# B130X.net
KiCad netlist of a schematic drawn in EAGLE
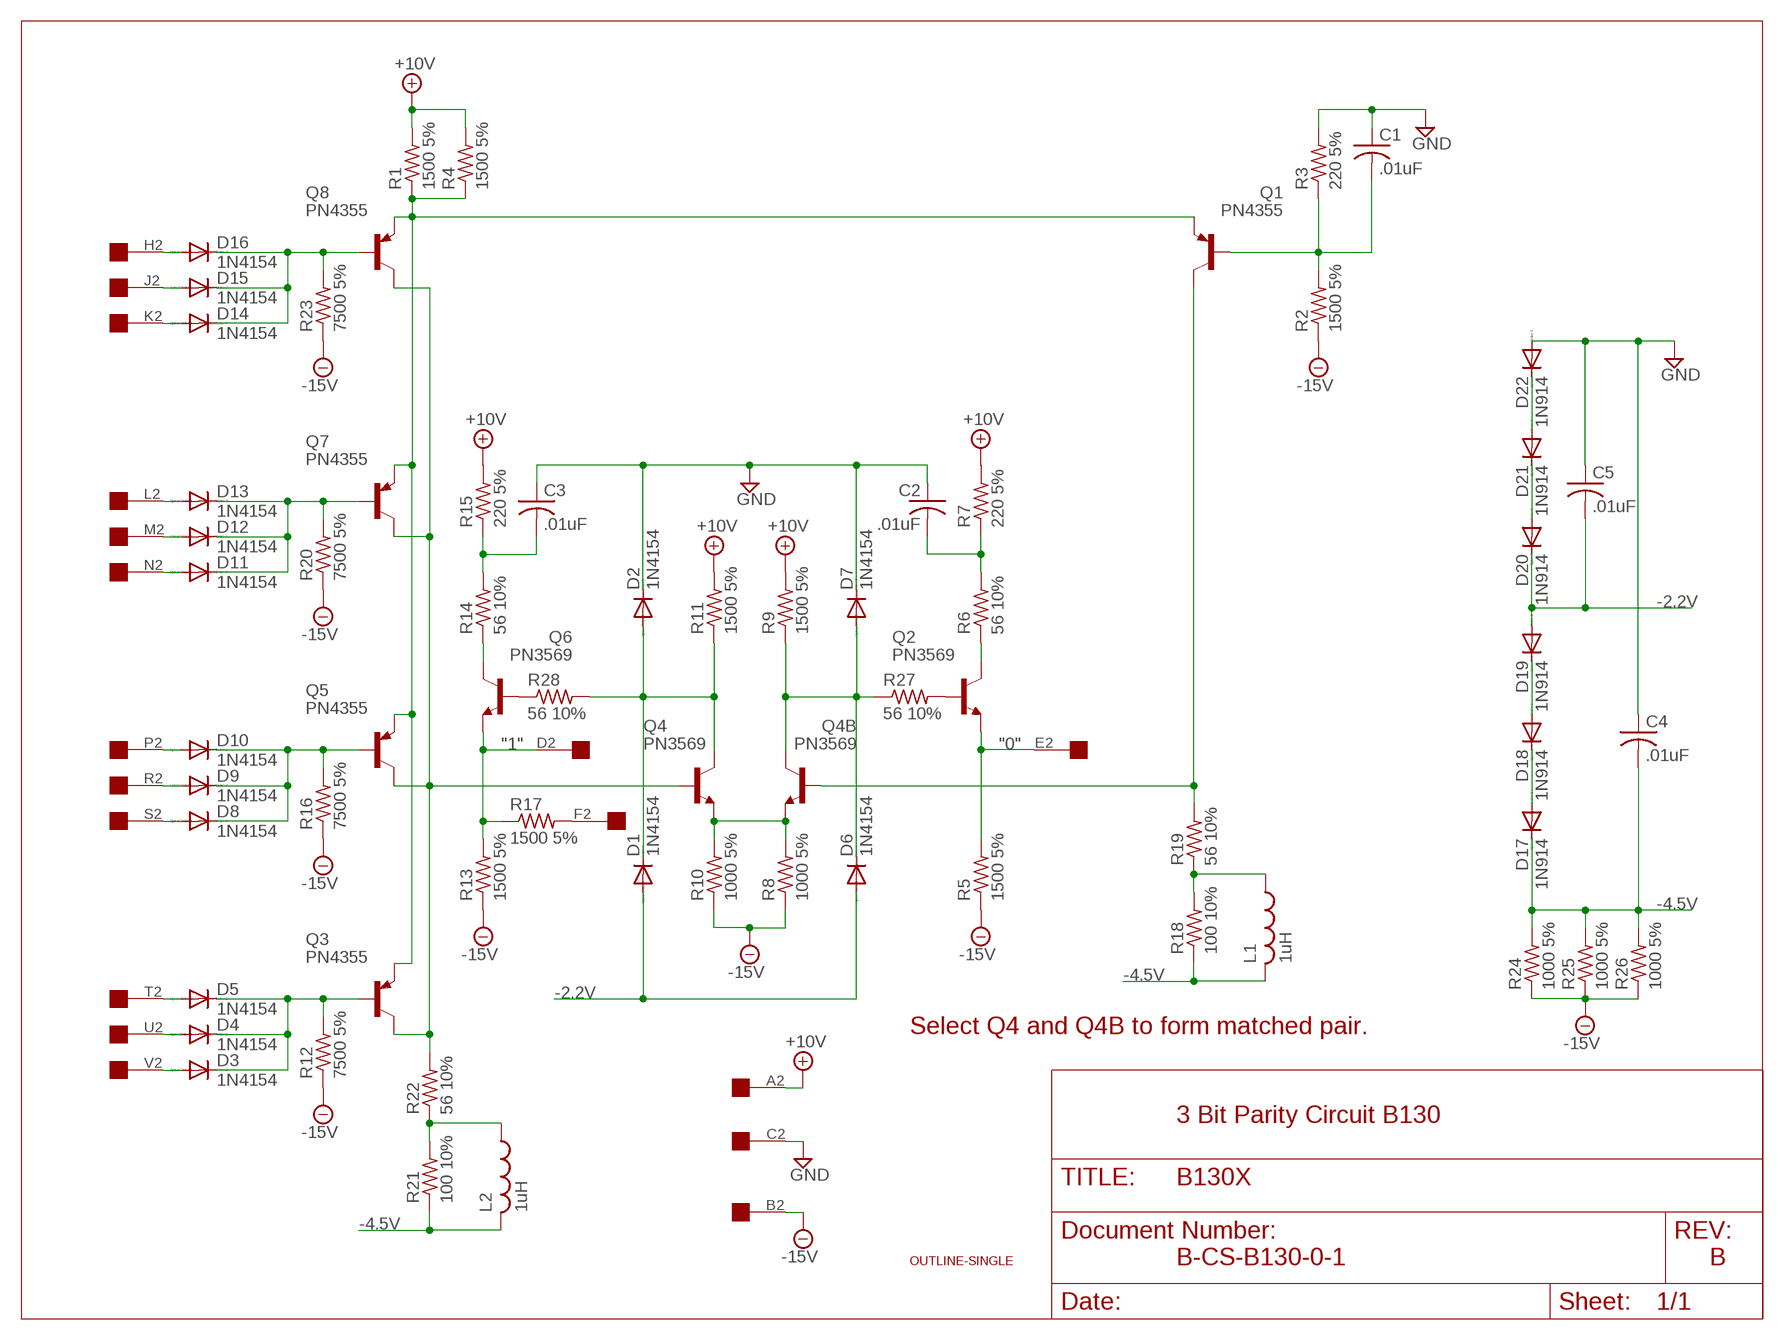
[diagram p0: schematic, sheet 1]

(export (version "E")
  (design (tool "Eeschema 10.0.6"))
  (components
    (comp (ref "C1")
      (value ".01uF")
      (footprint "eagle-import:C050-025X075")
      (libsource (lib "eagle-import") (part "C-US050-025X075"))
    )
    (comp (ref "C2")
      (value ".01uF")
      (footprint "eagle-import:C050-025X075")
      (libsource (lib "eagle-import") (part "C-US050-025X075"))
    )
    (comp (ref "C3")
      (value ".01uF")
      (footprint "eagle-import:C050-025X075")
      (libsource (lib "eagle-import") (part "C-US050-025X075"))
    )
    (comp (ref "C4")
      (value ".01uF")
      (footprint "eagle-import:C050-025X075")
      (libsource (lib "eagle-import") (part "C-US050-025X075"))
    )
    (comp (ref "C5")
      (value ".01uF")
      (footprint "eagle-import:C050-025X075")
      (libsource (lib "eagle-import") (part "C-US050-025X075"))
    )
    (comp (ref "D1")
      (value "1N4154")
      (footprint "eagle-import:DO35-10")
      (libsource (lib "eagle-import") (part "1N4148DO35-10"))
    )
    (comp (ref "D2")
      (value "1N4154")
      (footprint "eagle-import:DO35-10")
      (libsource (lib "eagle-import") (part "1N4148DO35-10"))
    )
    (comp (ref "D3")
      (value "1N4154")
      (footprint "eagle-import:DO35-10")
      (libsource (lib "eagle-import") (part "1N4148DO35-10"))
    )
    (comp (ref "D4")
      (value "1N4154")
      (footprint "eagle-import:DO35-10")
      (libsource (lib "eagle-import") (part "1N4148DO35-10"))
    )
    (comp (ref "D5")
      (value "1N4154")
      (footprint "eagle-import:DO35-10")
      (libsource (lib "eagle-import") (part "1N4148DO35-10"))
    )
    (comp (ref "D6")
      (value "1N4154")
      (footprint "eagle-import:DO35-10")
      (libsource (lib "eagle-import") (part "1N4148DO35-10"))
    )
    (comp (ref "D7")
      (value "1N4154")
      (footprint "eagle-import:DO35-10")
      (libsource (lib "eagle-import") (part "1N4148DO35-10"))
    )
    (comp (ref "D8")
      (value "1N4154")
      (footprint "eagle-import:DO35-10")
      (libsource (lib "eagle-import") (part "1N4148DO35-10"))
    )
    (comp (ref "D9")
      (value "1N4154")
      (footprint "eagle-import:DO35-10")
      (libsource (lib "eagle-import") (part "1N4148DO35-10"))
    )
    (comp (ref "D10")
      (value "1N4154")
      (footprint "eagle-import:DO35-10")
      (libsource (lib "eagle-import") (part "1N4148DO35-10"))
    )
    (comp (ref "D11")
      (value "1N4154")
      (footprint "eagle-import:DO35-10")
      (libsource (lib "eagle-import") (part "1N4148DO35-10"))
    )
    (comp (ref "D12")
      (value "1N4154")
      (footprint "eagle-import:DO35-10")
      (libsource (lib "eagle-import") (part "1N4148DO35-10"))
    )
    (comp (ref "D13")
      (value "1N4154")
      (footprint "eagle-import:DO35-10")
      (libsource (lib "eagle-import") (part "1N4148DO35-10"))
    )
    (comp (ref "D14")
      (value "1N4154")
      (footprint "eagle-import:DO35-10")
      (libsource (lib "eagle-import") (part "1N4148DO35-10"))
    )
    (comp (ref "D15")
      (value "1N4154")
      (footprint "eagle-import:DO35-10")
      (libsource (lib "eagle-import") (part "1N4148DO35-10"))
    )
    (comp (ref "D16")
      (value "1N4154")
      (footprint "eagle-import:DO35-10")
      (libsource (lib "eagle-import") (part "1N4148DO35-10"))
    )
    (comp (ref "D17")
      (value "1N914")
      (footprint "eagle-import:DO35-10")
      (libsource (lib "eagle-import") (part "1N4148DO35-10"))
    )
    (comp (ref "D18")
      (value "1N914")
      (footprint "eagle-import:DO35-10")
      (libsource (lib "eagle-import") (part "1N4148DO35-10"))
    )
    (comp (ref "D19")
      (value "1N914")
      (footprint "eagle-import:DO35-10")
      (libsource (lib "eagle-import") (part "1N4148DO35-10"))
    )
    (comp (ref "D20")
      (value "1N914")
      (footprint "eagle-import:DO35-10")
      (libsource (lib "eagle-import") (part "1N4148DO35-10"))
    )
    (comp (ref "D21")
      (value "1N914")
      (footprint "eagle-import:DO35-10")
      (libsource (lib "eagle-import") (part "1N4148DO35-10"))
    )
    (comp (ref "D22")
      (value "1N914")
      (footprint "eagle-import:DO35-10")
      (libsource (lib "eagle-import") (part "1N4148DO35-10"))
    )
    (comp (ref "L1")
      (value "1uH")
      (footprint "eagle-import:0207_10")
      (libsource (lib "eagle-import") (part "L-US0207/10"))
    )
    (comp (ref "L2")
      (value "1uH")
      (footprint "eagle-import:0207_10")
      (libsource (lib "eagle-import") (part "L-US0207/10"))
    )
    (comp (ref "Q1")
      (value "PN4355")
      (footprint "eagle-import:TO39")
      (libsource (lib "eagle-import") (part "2N2904"))
    )
    (comp (ref "Q2")
      (value "PN3569")
      (footprint "eagle-import:TO5")
      (libsource (lib "eagle-import") (part "2N2102"))
    )
    (comp (ref "Q3")
      (value "PN4355")
      (footprint "eagle-import:TO39")
      (libsource (lib "eagle-import") (part "2N2904"))
    )
    (comp (ref "Q4")
      (value "PN3569")
      (footprint "eagle-import:TO5")
      (libsource (lib "eagle-import") (part "2N2102"))
    )
    (comp (ref "Q4B")
      (value "PN3569")
      (footprint "eagle-import:TO5")
      (libsource (lib "eagle-import") (part "2N2102"))
    )
    (comp (ref "Q5")
      (value "PN4355")
      (footprint "eagle-import:TO39")
      (libsource (lib "eagle-import") (part "2N2904"))
    )
    (comp (ref "Q6")
      (value "PN3569")
      (footprint "eagle-import:TO5")
      (libsource (lib "eagle-import") (part "2N2102"))
    )
    (comp (ref "Q7")
      (value "PN4355")
      (footprint "eagle-import:TO39")
      (libsource (lib "eagle-import") (part "2N2904"))
    )
    (comp (ref "Q8")
      (value "PN4355")
      (footprint "eagle-import:TO39")
      (libsource (lib "eagle-import") (part "2N2904"))
    )
    (comp (ref "R1")
      (value "1500 5%")
      (footprint "eagle-import:0207_10")
      (libsource (lib "eagle-import") (part "R-US_0207/10"))
    )
    (comp (ref "R2")
      (value "1500 5%")
      (footprint "eagle-import:0207_10")
      (libsource (lib "eagle-import") (part "R-US_0207/10"))
    )
    (comp (ref "R3")
      (value "220 5%")
      (footprint "eagle-import:0207_10")
      (libsource (lib "eagle-import") (part "R-US_0207/10"))
    )
    (comp (ref "R4")
      (value "1500 5%")
      (footprint "eagle-import:0207_10")
      (libsource (lib "eagle-import") (part "R-US_0207/10"))
    )
    (comp (ref "R5")
      (value "1500 5%")
      (footprint "eagle-import:0207_10")
      (libsource (lib "eagle-import") (part "R-US_0207/10"))
    )
    (comp (ref "R6")
      (value "56 10%")
      (footprint "eagle-import:0207_10")
      (libsource (lib "eagle-import") (part "R-US_0207/10"))
    )
    (comp (ref "R7")
      (value "220 5%")
      (footprint "eagle-import:0207_10")
      (libsource (lib "eagle-import") (part "R-US_0207/10"))
    )
    (comp (ref "R8")
      (value "1000 5%")
      (footprint "eagle-import:0207_10")
      (libsource (lib "eagle-import") (part "R-US_0207/10"))
    )
    (comp (ref "R9")
      (value "1500 5%")
      (footprint "eagle-import:0207_10")
      (libsource (lib "eagle-import") (part "R-US_0207/10"))
    )
    (comp (ref "R10")
      (value "1000 5%")
      (footprint "eagle-import:0207_10")
      (libsource (lib "eagle-import") (part "R-US_0207/10"))
    )
    (comp (ref "R11")
      (value "1500 5%")
      (footprint "eagle-import:0207_10")
      (libsource (lib "eagle-import") (part "R-US_0207/10"))
    )
    (comp (ref "R12")
      (value "7500 5%")
      (footprint "eagle-import:0207_10")
      (libsource (lib "eagle-import") (part "R-US_0207/10"))
    )
    (comp (ref "R13")
      (value "1500 5%")
      (footprint "eagle-import:0207_10")
      (libsource (lib "eagle-import") (part "R-US_0207/10"))
    )
    (comp (ref "R14")
      (value "56 10%")
      (footprint "eagle-import:0207_10")
      (libsource (lib "eagle-import") (part "R-US_0207/10"))
    )
    (comp (ref "R15")
      (value "220 5%")
      (footprint "eagle-import:0207_10")
      (libsource (lib "eagle-import") (part "R-US_0207/10"))
    )
    (comp (ref "R16")
      (value "7500 5%")
      (footprint "eagle-import:0207_10")
      (libsource (lib "eagle-import") (part "R-US_0207/10"))
    )
    (comp (ref "R17")
      (value "1500 5%")
      (footprint "eagle-import:0207_10")
      (libsource (lib "eagle-import") (part "R-US_0207/10"))
    )
    (comp (ref "R18")
      (value "100 10%")
      (footprint "eagle-import:0207_10")
      (libsource (lib "eagle-import") (part "R-US_0207/10"))
    )
    (comp (ref "R19")
      (value "56 10%")
      (footprint "eagle-import:0207_10")
      (libsource (lib "eagle-import") (part "R-US_0207/10"))
    )
    (comp (ref "R20")
      (value "7500 5%")
      (footprint "eagle-import:0207_10")
      (libsource (lib "eagle-import") (part "R-US_0207/10"))
    )
    (comp (ref "R21")
      (value "100 10%")
      (footprint "eagle-import:0207_10")
      (libsource (lib "eagle-import") (part "R-US_0207/10"))
    )
    (comp (ref "R22")
      (value "56 10%")
      (footprint "eagle-import:0207_10")
      (libsource (lib "eagle-import") (part "R-US_0207/10"))
    )
    (comp (ref "R23")
      (value "7500 5%")
      (footprint "eagle-import:0207_10")
      (libsource (lib "eagle-import") (part "R-US_0207/10"))
    )
    (comp (ref "R24")
      (value "1000 5%")
      (footprint "eagle-import:0207_10")
      (libsource (lib "eagle-import") (part "R-US_0207/10"))
    )
    (comp (ref "R25")
      (value "1000 5%")
      (footprint "eagle-import:0207_10")
      (libsource (lib "eagle-import") (part "R-US_0207/10"))
    )
    (comp (ref "R26")
      (value "1000 5%")
      (footprint "eagle-import:0207_10")
      (libsource (lib "eagle-import") (part "R-US_0207/10"))
    )
    (comp (ref "R27")
      (value "56 10%")
      (footprint "eagle-import:0207_10")
      (libsource (lib "eagle-import") (part "R-US_0207/10"))
    )
    (comp (ref "R28")
      (value "56 10%")
      (footprint "eagle-import:0207_10")
      (libsource (lib "eagle-import") (part "R-US_0207/10"))
    )
    (comp (ref "U$1")
      (value "OUTLINE-SINGLE")
      (footprint "eagle-import:SINGLE")
      (libsource (lib "eagle-import") (part "OUTLINE-SINGLE"))
    )
    (comp (ref "U$2")
      (value "EDGE-1")
      (footprint "eagle-import:EDGE-CON1")
      (libsource (lib "eagle-import") (part "EDGE-1"))
    )
  )
  (nets
    (net (code "1") (name "+10V") (class "Default")
      (node (ref "R1") (pin "2") (pinfunction "2_2") (pintype "passive"))
      (node (ref "R11") (pin "2") (pinfunction "2_2") (pintype "passive"))
      (node (ref "R15") (pin "2") (pinfunction "2_2") (pintype "passive"))
      (node (ref "R4") (pin "2") (pinfunction "2_2") (pintype "passive"))
      (node (ref "R7") (pin "2") (pinfunction "2_2") (pintype "passive"))
      (node (ref "R9") (pin "2") (pinfunction "2_2") (pintype "passive"))
      (node (ref "U$2") (pin "A2") (pinfunction "1_A2") (pintype "bidirectional"))
    )
    (net (code "2") (name "-15V") (class "Default")
      (node (ref "R10") (pin "1") (pinfunction "1_1") (pintype "passive"))
      (node (ref "R12") (pin "1") (pinfunction "1_1") (pintype "passive"))
      (node (ref "R13") (pin "1") (pinfunction "1_1") (pintype "passive"))
      (node (ref "R16") (pin "1") (pinfunction "1_1") (pintype "passive"))
      (node (ref "R2") (pin "1") (pinfunction "1_1") (pintype "passive"))
      (node (ref "R20") (pin "1") (pinfunction "1_1") (pintype "passive"))
      (node (ref "R23") (pin "1") (pinfunction "1_1") (pintype "passive"))
      (node (ref "R24") (pin "1") (pinfunction "1_1") (pintype "passive"))
      (node (ref "R25") (pin "1") (pinfunction "1_1") (pintype "passive"))
      (node (ref "R26") (pin "1") (pinfunction "1_1") (pintype "passive"))
      (node (ref "R5") (pin "1") (pinfunction "1_1") (pintype "passive"))
      (node (ref "R8") (pin "1") (pinfunction "1_1") (pintype "passive"))
      (node (ref "U$2") (pin "B2") (pinfunction "1_B2") (pintype "bidirectional"))
    )
    (net (code "3") (name "/\"0\"") (class "Default")
      (node (ref "Q2") (pin "1") (pinfunction "E_1") (pintype "passive"))
      (node (ref "R5") (pin "2") (pinfunction "2_2") (pintype "passive"))
      (node (ref "U$2") (pin "E2") (pinfunction "1_E2") (pintype "bidirectional"))
    )
    (net (code "4") (name "/\"1\"") (class "Default")
      (node (ref "Q6") (pin "1") (pinfunction "E_1") (pintype "passive"))
      (node (ref "R13") (pin "2") (pinfunction "2_2") (pintype "passive"))
      (node (ref "R17") (pin "1") (pinfunction "1_1") (pintype "passive"))
      (node (ref "U$2") (pin "D2") (pinfunction "1_D2") (pintype "bidirectional"))
    )
    (net (code "5") (name "/-2.2V") (class "Default")
      (node (ref "C5") (pin "2") (pinfunction "2_2") (pintype "passive"))
      (node (ref "D1") (pin "A") (pinfunction "A_A") (pintype "passive"))
      (node (ref "D19") (pin "A") (pinfunction "A_A") (pintype "passive"))
      (node (ref "D20") (pin "C") (pinfunction "C_C") (pintype "passive"))
      (node (ref "D6") (pin "A") (pinfunction "A_A") (pintype "passive"))
    )
    (net (code "6") (name "/-4.5V") (class "Default")
      (node (ref "C4") (pin "2") (pinfunction "2_2") (pintype "passive"))
      (node (ref "D17") (pin "C") (pinfunction "C_C") (pintype "passive"))
      (node (ref "L1") (pin "2") (pinfunction "2_2") (pintype "passive"))
      (node (ref "L2") (pin "2") (pinfunction "2_2") (pintype "passive"))
      (node (ref "R18") (pin "1") (pinfunction "1_1") (pintype "passive"))
      (node (ref "R21") (pin "1") (pinfunction "1_1") (pintype "passive"))
      (node (ref "R24") (pin "2") (pinfunction "2_2") (pintype "passive"))
      (node (ref "R25") (pin "2") (pinfunction "2_2") (pintype "passive"))
      (node (ref "R26") (pin "2") (pinfunction "2_2") (pintype "passive"))
    )
    (net (code "7") (name "GND") (class "Default")
      (node (ref "C1") (pin "1") (pinfunction "1_1") (pintype "passive"))
      (node (ref "C2") (pin "1") (pinfunction "1_1") (pintype "passive"))
      (node (ref "C3") (pin "1") (pinfunction "1_1") (pintype "passive"))
      (node (ref "C4") (pin "1") (pinfunction "1_1") (pintype "passive"))
      (node (ref "C5") (pin "1") (pinfunction "1_1") (pintype "passive"))
      (node (ref "D2") (pin "C") (pinfunction "C_C") (pintype "passive"))
      (node (ref "D22") (pin "A") (pinfunction "A_A") (pintype "passive"))
      (node (ref "D7") (pin "C") (pinfunction "C_C") (pintype "passive"))
      (node (ref "R3") (pin "2") (pinfunction "2_2") (pintype "passive"))
      (node (ref "U$2") (pin "C2") (pinfunction "1_C2") (pintype "bidirectional"))
    )
    (net (code "8") (name "Net-(C2-Pad2)") (class "Default")
      (node (ref "C2") (pin "2") (pinfunction "2_2") (pintype "passive"))
      (node (ref "R6") (pin "2") (pinfunction "2_2") (pintype "passive"))
      (node (ref "R7") (pin "1") (pinfunction "1_1") (pintype "passive"))
    )
    (net (code "9") (name "Net-(C3-Pad2)") (class "Default")
      (node (ref "C3") (pin "2") (pinfunction "2_2") (pintype "passive"))
      (node (ref "R14") (pin "2") (pinfunction "2_2") (pintype "passive"))
      (node (ref "R15") (pin "1") (pinfunction "1_1") (pintype "passive"))
    )
    (net (code "10") (name "Net-(D17-PadA)") (class "Default")
      (node (ref "D17") (pin "A") (pinfunction "A_A") (pintype "passive"))
      (node (ref "D18") (pin "C") (pinfunction "C_C") (pintype "passive"))
    )
    (net (code "11") (name "Net-(D18-PadA)") (class "Default")
      (node (ref "D18") (pin "A") (pinfunction "A_A") (pintype "passive"))
      (node (ref "D19") (pin "C") (pinfunction "C_C") (pintype "passive"))
    )
    (net (code "12") (name "Net-(D20-PadA)") (class "Default")
      (node (ref "D20") (pin "A") (pinfunction "A_A") (pintype "passive"))
      (node (ref "D21") (pin "C") (pinfunction "C_C") (pintype "passive"))
    )
    (net (code "13") (name "Net-(D21-PadA)") (class "Default")
      (node (ref "D21") (pin "A") (pinfunction "A_A") (pintype "passive"))
      (node (ref "D22") (pin "C") (pinfunction "C_C") (pintype "passive"))
    )
    (net (code "14") (name "Net-(L1-Pad1)") (class "Default")
      (node (ref "L1") (pin "1") (pinfunction "1_1") (pintype "passive"))
      (node (ref "R18") (pin "2") (pinfunction "2_2") (pintype "passive"))
      (node (ref "R19") (pin "1") (pinfunction "1_1") (pintype "passive"))
    )
    (net (code "15") (name "Net-(L2-Pad1)") (class "Default")
      (node (ref "L2") (pin "1") (pinfunction "1_1") (pintype "passive"))
      (node (ref "R21") (pin "2") (pinfunction "2_2") (pintype "passive"))
      (node (ref "R22") (pin "1") (pinfunction "1_1") (pintype "passive"))
    )
    (net (code "16") (name "Net-(Q1-B)") (class "Default")
      (node (ref "C1") (pin "2") (pinfunction "2_2") (pintype "passive"))
      (node (ref "Q1") (pin "2") (pinfunction "B_2") (pintype "passive"))
      (node (ref "R2") (pin "2") (pinfunction "2_2") (pintype "passive"))
      (node (ref "R3") (pin "1") (pinfunction "1_1") (pintype "passive"))
    )
    (net (code "17") (name "Net-(Q1-C)") (class "Default")
      (node (ref "Q1") (pin "3") (pinfunction "C_3") (pintype "passive"))
      (node (ref "Q4B") (pin "2") (pinfunction "B_2") (pintype "passive"))
      (node (ref "R19") (pin "2") (pinfunction "2_2") (pintype "passive"))
    )
    (net (code "18") (name "Net-(Q1-E)") (class "Default")
      (node (ref "Q1") (pin "1") (pinfunction "E_1") (pintype "passive"))
      (node (ref "Q3") (pin "1") (pinfunction "E_1") (pintype "passive"))
      (node (ref "Q5") (pin "1") (pinfunction "E_1") (pintype "passive"))
      (node (ref "Q7") (pin "1") (pinfunction "E_1") (pintype "passive"))
      (node (ref "Q8") (pin "1") (pinfunction "E_1") (pintype "passive"))
      (node (ref "R1") (pin "1") (pinfunction "1_1") (pintype "passive"))
      (node (ref "R4") (pin "1") (pinfunction "1_1") (pintype "passive"))
    )
    (net (code "19") (name "Net-(Q2-B)") (class "Default")
      (node (ref "Q2") (pin "2") (pinfunction "B_2") (pintype "passive"))
      (node (ref "R27") (pin "2") (pinfunction "2_2") (pintype "passive"))
    )
    (net (code "20") (name "Net-(Q2-C)") (class "Default")
      (node (ref "Q2") (pin "3") (pinfunction "C_3") (pintype "passive"))
      (node (ref "R6") (pin "1") (pinfunction "1_1") (pintype "passive"))
    )
    (net (code "21") (name "Net-(Q3-B)") (class "Default")
      (node (ref "D3") (pin "C") (pinfunction "C_C") (pintype "passive"))
      (node (ref "D4") (pin "C") (pinfunction "C_C") (pintype "passive"))
      (node (ref "D5") (pin "C") (pinfunction "C_C") (pintype "passive"))
      (node (ref "Q3") (pin "2") (pinfunction "B_2") (pintype "passive"))
      (node (ref "R12") (pin "2") (pinfunction "2_2") (pintype "passive"))
    )
    (net (code "22") (name "Net-(Q3-C)") (class "Default")
      (node (ref "Q3") (pin "3") (pinfunction "C_3") (pintype "passive"))
      (node (ref "Q4") (pin "2") (pinfunction "B_2") (pintype "passive"))
      (node (ref "Q5") (pin "3") (pinfunction "C_3") (pintype "passive"))
      (node (ref "Q7") (pin "3") (pinfunction "C_3") (pintype "passive"))
      (node (ref "Q8") (pin "3") (pinfunction "C_3") (pintype "passive"))
      (node (ref "R22") (pin "2") (pinfunction "2_2") (pintype "passive"))
    )
    (net (code "23") (name "Net-(Q4-C)") (class "Default")
      (node (ref "D1") (pin "C") (pinfunction "C_C") (pintype "passive"))
      (node (ref "D2") (pin "A") (pinfunction "A_A") (pintype "passive"))
      (node (ref "Q4") (pin "3") (pinfunction "C_3") (pintype "passive"))
      (node (ref "R11") (pin "1") (pinfunction "1_1") (pintype "passive"))
      (node (ref "R28") (pin "2") (pinfunction "2_2") (pintype "passive"))
    )
    (net (code "24") (name "Net-(Q4-E)") (class "Default")
      (node (ref "Q4") (pin "1") (pinfunction "E_1") (pintype "passive"))
      (node (ref "Q4B") (pin "1") (pinfunction "E_1") (pintype "passive"))
      (node (ref "R10") (pin "2") (pinfunction "2_2") (pintype "passive"))
      (node (ref "R8") (pin "2") (pinfunction "2_2") (pintype "passive"))
    )
    (net (code "25") (name "Net-(Q4B-C)") (class "Default")
      (node (ref "D6") (pin "C") (pinfunction "C_C") (pintype "passive"))
      (node (ref "D7") (pin "A") (pinfunction "A_A") (pintype "passive"))
      (node (ref "Q4B") (pin "3") (pinfunction "C_3") (pintype "passive"))
      (node (ref "R27") (pin "1") (pinfunction "1_1") (pintype "passive"))
      (node (ref "R9") (pin "1") (pinfunction "1_1") (pintype "passive"))
    )
    (net (code "26") (name "Net-(Q5-B)") (class "Default")
      (node (ref "D10") (pin "C") (pinfunction "C_C") (pintype "passive"))
      (node (ref "D8") (pin "C") (pinfunction "C_C") (pintype "passive"))
      (node (ref "D9") (pin "C") (pinfunction "C_C") (pintype "passive"))
      (node (ref "Q5") (pin "2") (pinfunction "B_2") (pintype "passive"))
      (node (ref "R16") (pin "2") (pinfunction "2_2") (pintype "passive"))
    )
    (net (code "27") (name "Net-(Q6-B)") (class "Default")
      (node (ref "Q6") (pin "2") (pinfunction "B_2") (pintype "passive"))
      (node (ref "R28") (pin "1") (pinfunction "1_1") (pintype "passive"))
    )
    (net (code "28") (name "Net-(Q6-C)") (class "Default")
      (node (ref "Q6") (pin "3") (pinfunction "C_3") (pintype "passive"))
      (node (ref "R14") (pin "1") (pinfunction "1_1") (pintype "passive"))
    )
    (net (code "29") (name "Net-(Q7-B)") (class "Default")
      (node (ref "D11") (pin "C") (pinfunction "C_C") (pintype "passive"))
      (node (ref "D12") (pin "C") (pinfunction "C_C") (pintype "passive"))
      (node (ref "D13") (pin "C") (pinfunction "C_C") (pintype "passive"))
      (node (ref "Q7") (pin "2") (pinfunction "B_2") (pintype "passive"))
      (node (ref "R20") (pin "2") (pinfunction "2_2") (pintype "passive"))
    )
    (net (code "30") (name "Net-(Q8-B)") (class "Default")
      (node (ref "D14") (pin "C") (pinfunction "C_C") (pintype "passive"))
      (node (ref "D15") (pin "C") (pinfunction "C_C") (pintype "passive"))
      (node (ref "D16") (pin "C") (pinfunction "C_C") (pintype "passive"))
      (node (ref "Q8") (pin "2") (pinfunction "B_2") (pintype "passive"))
      (node (ref "R23") (pin "2") (pinfunction "2_2") (pintype "passive"))
    )
    (net (code "31") (name "Net-(U$2F-1)") (class "Default")
      (node (ref "R17") (pin "2") (pinfunction "2_2") (pintype "passive"))
      (node (ref "U$2") (pin "F2") (pinfunction "1_F2") (pintype "bidirectional"))
    )
    (net (code "32") (name "Net-(U$2G-1)") (class "Default")
      (node (ref "D16") (pin "A") (pinfunction "A_A") (pintype "passive"))
      (node (ref "U$2") (pin "H2") (pinfunction "1_H2") (pintype "bidirectional"))
    )
    (net (code "33") (name "Net-(U$2H-1)") (class "Default")
      (node (ref "D15") (pin "A") (pinfunction "A_A") (pintype "passive"))
      (node (ref "U$2") (pin "J2") (pinfunction "1_J2") (pintype "bidirectional"))
    )
    (net (code "34") (name "Net-(U$2I-1)") (class "Default")
      (node (ref "D14") (pin "A") (pinfunction "A_A") (pintype "passive"))
      (node (ref "U$2") (pin "K2") (pinfunction "1_K2") (pintype "bidirectional"))
    )
    (net (code "35") (name "Net-(U$2J-1)") (class "Default")
      (node (ref "D13") (pin "A") (pinfunction "A_A") (pintype "passive"))
      (node (ref "U$2") (pin "L2") (pinfunction "1_L2") (pintype "bidirectional"))
    )
    (net (code "36") (name "Net-(U$2K-1)") (class "Default")
      (node (ref "D12") (pin "A") (pinfunction "A_A") (pintype "passive"))
      (node (ref "U$2") (pin "M2") (pinfunction "1_M2") (pintype "bidirectional"))
    )
    (net (code "37") (name "Net-(U$2L-1)") (class "Default")
      (node (ref "D11") (pin "A") (pinfunction "A_A") (pintype "passive"))
      (node (ref "U$2") (pin "N2") (pinfunction "1_N2") (pintype "bidirectional"))
    )
    (net (code "38") (name "Net-(U$2M-1)") (class "Default")
      (node (ref "D10") (pin "A") (pinfunction "A_A") (pintype "passive"))
      (node (ref "U$2") (pin "P2") (pinfunction "1_P2") (pintype "bidirectional"))
    )
    (net (code "39") (name "Net-(U$2N-1)") (class "Default")
      (node (ref "D9") (pin "A") (pinfunction "A_A") (pintype "passive"))
      (node (ref "U$2") (pin "R2") (pinfunction "1_R2") (pintype "bidirectional"))
    )
    (net (code "40") (name "Net-(U$2O-1)") (class "Default")
      (node (ref "D8") (pin "A") (pinfunction "A_A") (pintype "passive"))
      (node (ref "U$2") (pin "S2") (pinfunction "1_S2") (pintype "bidirectional"))
    )
    (net (code "41") (name "Net-(U$2P-1)") (class "Default")
      (node (ref "D5") (pin "A") (pinfunction "A_A") (pintype "passive"))
      (node (ref "U$2") (pin "T2") (pinfunction "1_T2") (pintype "bidirectional"))
    )
    (net (code "42") (name "Net-(U$2Q-1)") (class "Default")
      (node (ref "D4") (pin "A") (pinfunction "A_A") (pintype "passive"))
      (node (ref "U$2") (pin "U2") (pinfunction "1_U2") (pintype "bidirectional"))
    )
    (net (code "43") (name "Net-(U$2R-1)") (class "Default")
      (node (ref "D3") (pin "A") (pinfunction "A_A") (pintype "passive"))
      (node (ref "U$2") (pin "V2") (pinfunction "1_V2") (pintype "bidirectional"))
    )
  )
)
